# rearamp3210105209.net
KiCad netlist of a schematic drawn in Altium Designer
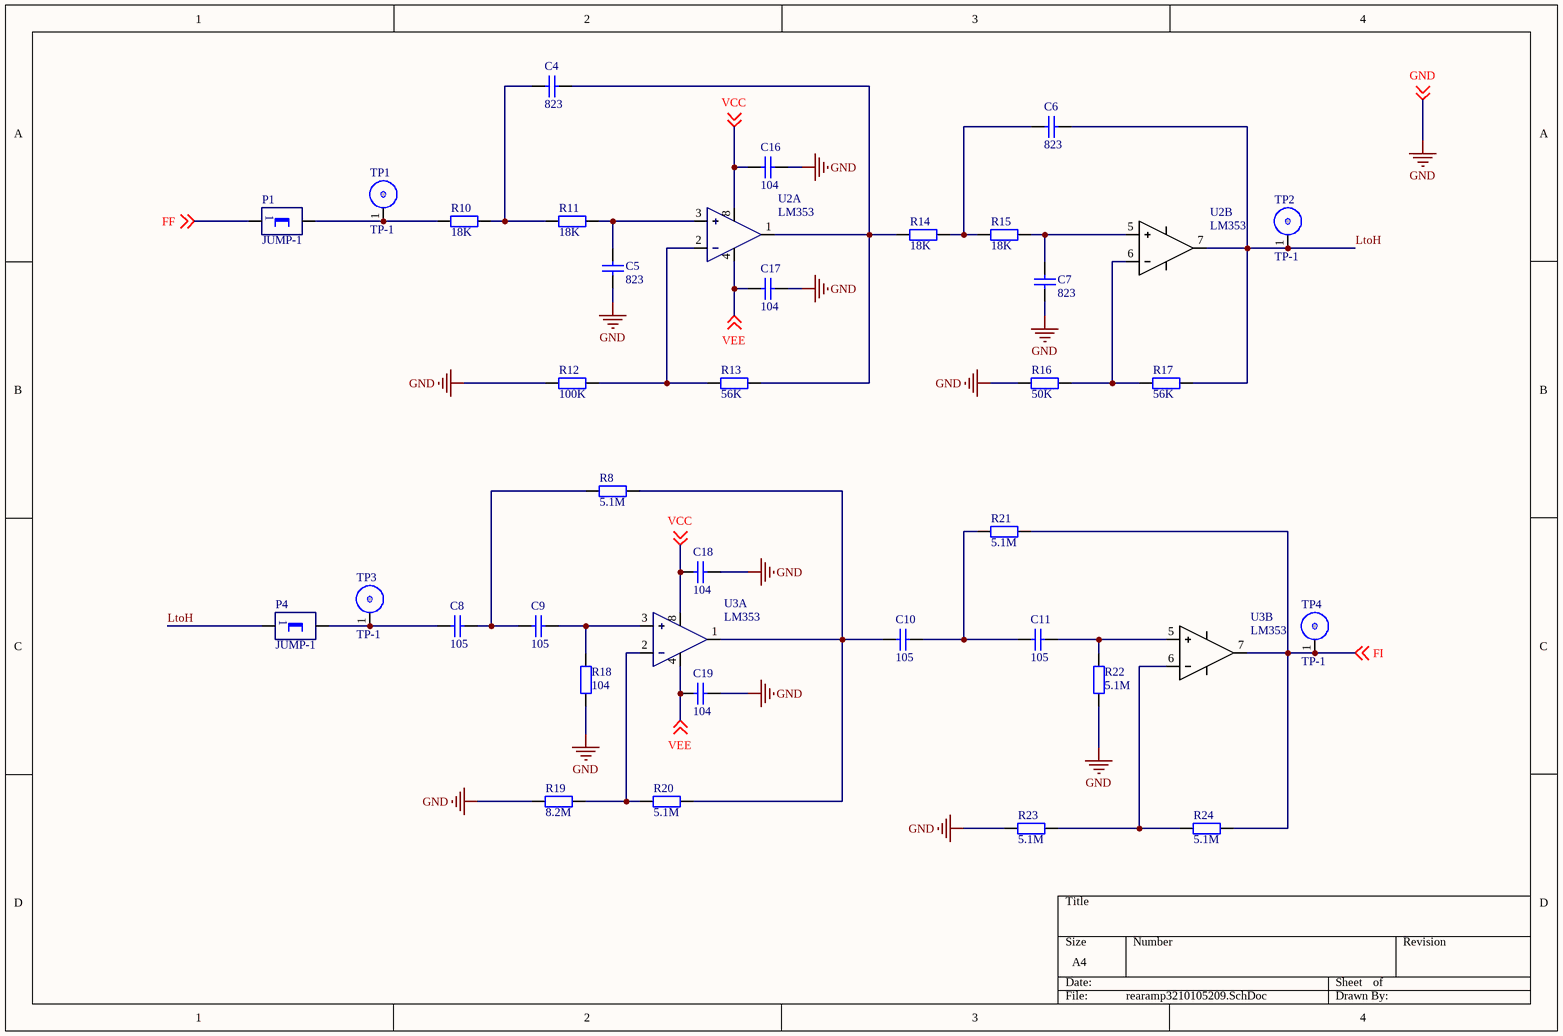
[diagram p0: rearamp3210105209.SchDoc]

(export (version "E")
  (design (tool "Eeschema 10.0.6"))
  (components
    (comp (ref "C4")
      (value "823")
      (footprint "C2")
      (description "Capacitor")
      (fields (field (name "PUBLISHER") "Altium Limited"))
      (libsource (lib "ECG2.0") (part "Cap"))
    )
    (comp (ref "C5")
      (value "823")
      (footprint "C2")
      (description "Capacitor")
      (fields (field (name "PUBLISHER") "Altium Limited"))
      (libsource (lib "ECG2.0") (part "Cap"))
    )
    (comp (ref "C6")
      (value "823")
      (footprint "C2")
      (description "Capacitor")
      (fields (field (name "PUBLISHER") "Altium Limited"))
      (libsource (lib "ECG2.0") (part "Cap"))
    )
    (comp (ref "C7")
      (value "823")
      (footprint "C2")
      (description "Capacitor")
      (fields (field (name "PUBLISHER") "Altium Limited"))
      (libsource (lib "ECG2.0") (part "Cap"))
    )
    (comp (ref "C8")
      (value "105")
      (footprint "C2")
      (description "Capacitor")
      (fields (field (name "PUBLISHER") "Altium Limited"))
      (libsource (lib "ECG2.0") (part "Cap"))
    )
    (comp (ref "C9")
      (value "105")
      (footprint "C2")
      (description "Capacitor")
      (fields (field (name "PUBLISHER") "Altium Limited"))
      (libsource (lib "ECG2.0") (part "Cap"))
    )
    (comp (ref "C10")
      (value "105")
      (footprint "C2")
      (description "Capacitor")
      (fields (field (name "PUBLISHER") "Altium Limited"))
      (libsource (lib "ECG2.0") (part "Cap"))
    )
    (comp (ref "C11")
      (value "105")
      (footprint "C2")
      (description "Capacitor")
      (fields (field (name "PUBLISHER") "Altium Limited"))
      (libsource (lib "ECG2.0") (part "Cap"))
    )
    (comp (ref "C16")
      (value "104")
      (footprint "C2")
      (description "Capacitor")
      (fields (field (name "PUBLISHER") "Altium Limited"))
      (libsource (lib "ECG2.0") (part "Cap"))
    )
    (comp (ref "C17")
      (value "104")
      (footprint "C2")
      (description "Capacitor")
      (fields (field (name "PUBLISHER") "Altium Limited"))
      (libsource (lib "ECG2.0") (part "Cap"))
    )
    (comp (ref "C18")
      (value "104")
      (footprint "C2")
      (description "Capacitor")
      (fields (field (name "PUBLISHER") "Altium Limited"))
      (libsource (lib "ECG2.0") (part "Cap"))
    )
    (comp (ref "C19")
      (value "104")
      (footprint "C2")
      (description "Capacitor")
      (fields (field (name "PUBLISHER") "Altium Limited"))
      (libsource (lib "ECG2.0") (part "Cap"))
    )
    (comp (ref "P1") (value "JUMP-1") (footprint "SIP2") (libsource (lib "ECG2.0") (part "JUMP-1")))
    (comp (ref "P4") (value "JUMP-1") (footprint "SIP2") (libsource (lib "ECG2.0") (part "JUMP-1")))
    (comp (ref "R8")
      (value "5.1M")
      (footprint "AXIAL-0.3")
      (description "Resistor")
      (fields (field (name "PUBLISHER") "Altium Limited"))
      (libsource (lib "ECG2.0") (part "Res2"))
    )
    (comp (ref "R10")
      (value "18K")
      (footprint "AXIAL-0.3")
      (description "Resistor")
      (fields (field (name "PUBLISHER") "Altium Limited"))
      (libsource (lib "ECG2.0") (part "Res2"))
    )
    (comp (ref "R11")
      (value "18K")
      (footprint "AXIAL-0.3")
      (description "Resistor")
      (fields (field (name "PUBLISHER") "Altium Limited"))
      (libsource (lib "ECG2.0") (part "Res2"))
    )
    (comp (ref "R12")
      (value "100K")
      (footprint "AXIAL-0.3")
      (description "Resistor")
      (fields (field (name "PUBLISHER") "Altium Limited"))
      (libsource (lib "ECG2.0") (part "Res2"))
    )
    (comp (ref "R13")
      (value "56K")
      (footprint "AXIAL-0.3")
      (description "Resistor")
      (fields (field (name "PUBLISHER") "Altium Limited"))
      (libsource (lib "ECG2.0") (part "Res2"))
    )
    (comp (ref "R14")
      (value "18K")
      (footprint "AXIAL-0.3")
      (description "Resistor")
      (fields (field (name "PUBLISHER") "Altium Limited"))
      (libsource (lib "ECG2.0") (part "Res2"))
    )
    (comp (ref "R15")
      (value "18K")
      (footprint "AXIAL-0.3")
      (description "Resistor")
      (fields (field (name "PUBLISHER") "Altium Limited"))
      (libsource (lib "ECG2.0") (part "Res2"))
    )
    (comp (ref "R16")
      (value "50K")
      (footprint "AXIAL-0.3")
      (description "Resistor")
      (fields (field (name "PUBLISHER") "Altium Limited"))
      (libsource (lib "ECG2.0") (part "Res2"))
    )
    (comp (ref "R17")
      (value "56K")
      (footprint "AXIAL-0.3")
      (description "Resistor")
      (fields (field (name "PUBLISHER") "Altium Limited"))
      (libsource (lib "ECG2.0") (part "Res2"))
    )
    (comp (ref "R18")
      (value "104")
      (footprint "AXIAL-0.3")
      (description "Resistor")
      (fields (field (name "PUBLISHER") "Altium Limited"))
      (libsource (lib "") (part "Res2_1"))
    )
    (comp (ref "R19")
      (value "8.2M")
      (footprint "AXIAL-0.3")
      (description "Resistor")
      (fields (field (name "PUBLISHER") "Altium Limited"))
      (libsource (lib "ECG2.0") (part "Res2"))
    )
    (comp (ref "R20")
      (value "5.1M")
      (footprint "AXIAL-0.3")
      (description "Resistor")
      (fields (field (name "PUBLISHER") "Altium Limited"))
      (libsource (lib "ECG2.0") (part "Res2"))
    )
    (comp (ref "R21")
      (value "5.1M")
      (footprint "AXIAL-0.3")
      (description "Resistor")
      (fields (field (name "PUBLISHER") "Altium Limited"))
      (libsource (lib "ECG2.0") (part "Res2"))
    )
    (comp (ref "R22")
      (value "5.1M")
      (footprint "AXIAL-0.3")
      (description "Resistor")
      (fields (field (name "PUBLISHER") "Altium Limited"))
      (libsource (lib "") (part "Res2_1"))
    )
    (comp (ref "R23")
      (value "5.1M")
      (footprint "AXIAL-0.3")
      (description "Resistor")
      (fields (field (name "PUBLISHER") "Altium Limited"))
      (libsource (lib "ECG2.0") (part "Res2"))
    )
    (comp (ref "R24")
      (value "5.1M")
      (footprint "AXIAL-0.3")
      (description "Resistor")
      (fields (field (name "PUBLISHER") "Altium Limited"))
      (libsource (lib "ECG2.0") (part "Res2"))
    )
    (comp (ref "TP1") (value "TP-1") (footprint "tp-1-1") (libsource (lib "ECG2.0") (part "TP-1")))
    (comp (ref "TP2") (value "TP-1") (footprint "tp-1-1") (libsource (lib "ECG2.0") (part "TP-1")))
    (comp (ref "TP3") (value "TP-1") (footprint "tp-1-1") (libsource (lib "ECG2.0") (part "TP-1")))
    (comp (ref "TP4") (value "TP-1") (footprint "tp-1-1") (libsource (lib "ECG2.0") (part "TP-1")))
    (comp (ref "U2") (value "LM353") (footprint "DIP8") (libsource (lib "ECG2.0") (part "LM353")))
    (comp (ref "U3") (value "LM353") (footprint "DIP8") (libsource (lib "ECG2.0") (part "LM353")))
  )
  (nets
    (net (code "1") (name "/LtoH") (class "Default")
      (node (ref "C6") (pin "2") (pinfunction "2_2") (pintype "passive"))
      (node (ref "P4") (pin "1") (pinfunction "1_1") (pintype "passive"))
      (node (ref "R17") (pin "2") (pinfunction "2_2") (pintype "passive"))
      (node (ref "TP2") (pin "1") (pintype "passive"))
      (node (ref "U2") (pin "7") (pinfunction "7_7") (pintype "passive"))
    )
    (net (code "2") (name "FF") (class "Default")
      (node (ref "P1") (pin "1") (pinfunction "1_1") (pintype "passive"))
    )
    (net (code "3") (name "FI") (class "Default")
      (node (ref "R21") (pin "2") (pinfunction "2_2") (pintype "passive"))
      (node (ref "R24") (pin "2") (pinfunction "2_2") (pintype "passive"))
      (node (ref "TP4") (pin "1") (pintype "passive"))
      (node (ref "U3") (pin "7") (pinfunction "7_7") (pintype "passive"))
    )
    (net (code "4") (name "GND") (class "Default")
      (node (ref "C16") (pin "2") (pinfunction "2_2") (pintype "passive"))
      (node (ref "C17") (pin "2") (pinfunction "2_2") (pintype "passive"))
      (node (ref "C18") (pin "2") (pinfunction "2_2") (pintype "passive"))
      (node (ref "C19") (pin "2") (pinfunction "2_2") (pintype "passive"))
      (node (ref "C5") (pin "1") (pinfunction "1_1") (pintype "passive"))
      (node (ref "C7") (pin "1") (pinfunction "1_1") (pintype "passive"))
      (node (ref "R12") (pin "1") (pinfunction "1_1") (pintype "passive"))
      (node (ref "R16") (pin "1") (pinfunction "1_1") (pintype "passive"))
      (node (ref "R18") (pin "1") (pinfunction "1_1") (pintype "passive"))
      (node (ref "R19") (pin "1") (pinfunction "1_1") (pintype "passive"))
      (node (ref "R22") (pin "1") (pinfunction "1_1") (pintype "passive"))
      (node (ref "R23") (pin "1") (pinfunction "1_1") (pintype "passive"))
    )
    (net (code "5") (name "Net-(C4-Pad1)") (class "Default")
      (node (ref "C4") (pin "1") (pinfunction "1_1") (pintype "passive"))
      (node (ref "R10") (pin "2") (pinfunction "2_2") (pintype "passive"))
      (node (ref "R11") (pin "1") (pinfunction "1_1") (pintype "passive"))
    )
    (net (code "6") (name "Net-(C4-Pad2)") (class "Default")
      (node (ref "C4") (pin "2") (pinfunction "2_2") (pintype "passive"))
      (node (ref "R13") (pin "2") (pinfunction "2_2") (pintype "passive"))
      (node (ref "R14") (pin "1") (pinfunction "1_1") (pintype "passive"))
      (node (ref "U2") (pin "1") (pinfunction "1_1") (pintype "passive"))
    )
    (net (code "7") (name "Net-(C5-Pad2)") (class "Default")
      (node (ref "C5") (pin "2") (pinfunction "2_2") (pintype "passive"))
      (node (ref "R11") (pin "2") (pinfunction "2_2") (pintype "passive"))
      (node (ref "U2") (pin "3") (pinfunction "3_3") (pintype "passive"))
    )
    (net (code "8") (name "Net-(C6-Pad1)") (class "Default")
      (node (ref "C6") (pin "1") (pinfunction "1_1") (pintype "passive"))
      (node (ref "R14") (pin "2") (pinfunction "2_2") (pintype "passive"))
      (node (ref "R15") (pin "1") (pinfunction "1_1") (pintype "passive"))
    )
    (net (code "9") (name "Net-(C7-Pad2)") (class "Default")
      (node (ref "C7") (pin "2") (pinfunction "2_2") (pintype "passive"))
      (node (ref "R15") (pin "2") (pinfunction "2_2") (pintype "passive"))
      (node (ref "U2") (pin "5") (pinfunction "5_5") (pintype "passive"))
    )
    (net (code "10") (name "Net-(C8-Pad1)") (class "Default")
      (node (ref "C8") (pin "1") (pinfunction "1_1") (pintype "passive"))
      (node (ref "P4") (pin "2") (pintype "passive"))
      (node (ref "TP3") (pin "1") (pintype "passive"))
    )
    (net (code "11") (name "Net-(C8-Pad2)") (class "Default")
      (node (ref "C8") (pin "2") (pinfunction "2_2") (pintype "passive"))
      (node (ref "C9") (pin "1") (pinfunction "1_1") (pintype "passive"))
      (node (ref "R8") (pin "1") (pinfunction "1_1") (pintype "passive"))
    )
    (net (code "12") (name "Net-(C9-Pad2)") (class "Default")
      (node (ref "C9") (pin "2") (pinfunction "2_2") (pintype "passive"))
      (node (ref "R18") (pin "2") (pinfunction "2_2") (pintype "passive"))
      (node (ref "U3") (pin "3") (pinfunction "3_3") (pintype "passive"))
    )
    (net (code "13") (name "Net-(C10-Pad1)") (class "Default")
      (node (ref "C10") (pin "1") (pinfunction "1_1") (pintype "passive"))
      (node (ref "R20") (pin "2") (pinfunction "2_2") (pintype "passive"))
      (node (ref "R8") (pin "2") (pinfunction "2_2") (pintype "passive"))
      (node (ref "U3") (pin "1") (pinfunction "1_1") (pintype "passive"))
    )
    (net (code "14") (name "Net-(C10-Pad2)") (class "Default")
      (node (ref "C10") (pin "2") (pinfunction "2_2") (pintype "passive"))
      (node (ref "C11") (pin "1") (pinfunction "1_1") (pintype "passive"))
      (node (ref "R21") (pin "1") (pinfunction "1_1") (pintype "passive"))
    )
    (net (code "15") (name "Net-(C11-Pad2)") (class "Default")
      (node (ref "C11") (pin "2") (pinfunction "2_2") (pintype "passive"))
      (node (ref "R22") (pin "2") (pinfunction "2_2") (pintype "passive"))
      (node (ref "U3") (pin "5") (pinfunction "5_5") (pintype "passive"))
    )
    (net (code "16") (name "Net-(P1-Pad2)") (class "Default")
      (node (ref "P1") (pin "2") (pintype "passive"))
      (node (ref "R10") (pin "1") (pinfunction "1_1") (pintype "passive"))
      (node (ref "TP1") (pin "1") (pintype "passive"))
    )
    (net (code "17") (name "Net-(R12-Pad2)") (class "Default")
      (node (ref "R12") (pin "2") (pinfunction "2_2") (pintype "passive"))
      (node (ref "R13") (pin "1") (pinfunction "1_1") (pintype "passive"))
      (node (ref "U2") (pin "2") (pinfunction "2_2") (pintype "passive"))
    )
    (net (code "18") (name "Net-(R16-Pad2)") (class "Default")
      (node (ref "R16") (pin "2") (pinfunction "2_2") (pintype "passive"))
      (node (ref "R17") (pin "1") (pinfunction "1_1") (pintype "passive"))
      (node (ref "U2") (pin "6") (pinfunction "6_6") (pintype "passive"))
    )
    (net (code "19") (name "Net-(R19-Pad2)") (class "Default")
      (node (ref "R19") (pin "2") (pinfunction "2_2") (pintype "passive"))
      (node (ref "R20") (pin "1") (pinfunction "1_1") (pintype "passive"))
      (node (ref "U3") (pin "2") (pinfunction "2_2") (pintype "passive"))
    )
    (net (code "20") (name "Net-(R23-Pad2)") (class "Default")
      (node (ref "R23") (pin "2") (pinfunction "2_2") (pintype "passive"))
      (node (ref "R24") (pin "1") (pinfunction "1_1") (pintype "passive"))
      (node (ref "U3") (pin "6") (pinfunction "6_6") (pintype "passive"))
    )
    (net (code "21") (name "VCC") (class "Default")
      (node (ref "C16") (pin "1") (pinfunction "1_1") (pintype "passive"))
      (node (ref "C18") (pin "1") (pinfunction "1_1") (pintype "passive"))
      (node (ref "U2") (pin "8") (pinfunction "8_8") (pintype "passive"))
      (node (ref "U3") (pin "8") (pinfunction "8_8") (pintype "passive"))
    )
    (net (code "22") (name "VEE") (class "Default")
      (node (ref "C17") (pin "1") (pinfunction "1_1") (pintype "passive"))
      (node (ref "C19") (pin "1") (pinfunction "1_1") (pintype "passive"))
      (node (ref "U2") (pin "4") (pinfunction "4_4") (pintype "passive"))
      (node (ref "U3") (pin "4") (pinfunction "4_4") (pintype "passive"))
    )
  )
)
